# testboard_chip1_poling.net
KiCad netlist of a schematic drawn in Altium Designer
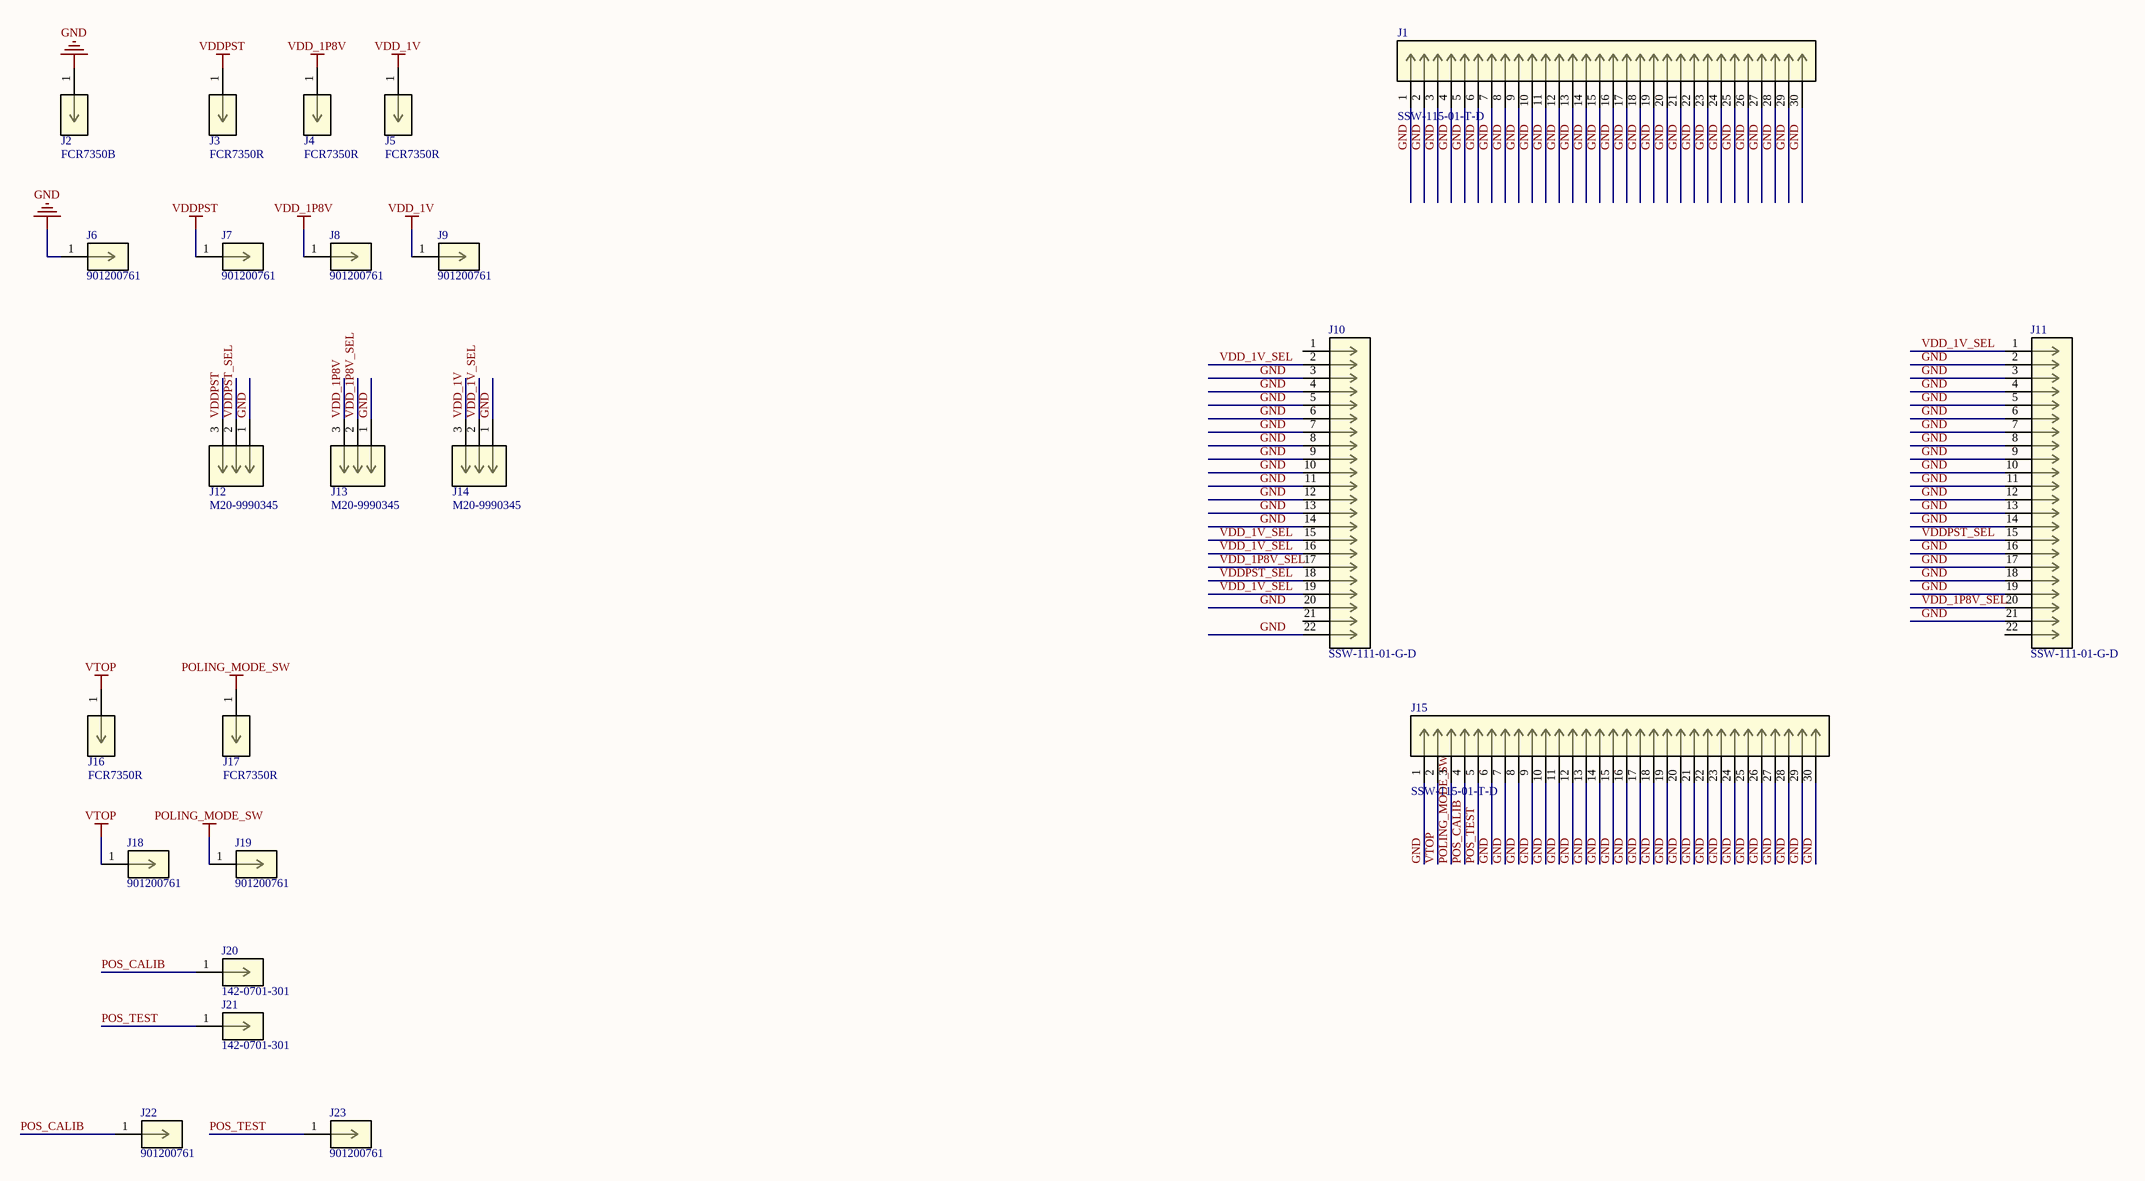
[diagram p0: testboard_chip1_poling.SchDoc]

(export (version "E")
  (design (tool "Eeschema 10.0.6"))
  (components
    (comp (ref "J1")
      (value "SSW-115-01-T-D")
      (footprint "CON30_2X15_TU_SSQ")
      (description "No Description Available")
      (fields (field (name "COPYRIGHT") "Copyright (C) 2022 Ultra Librarian. All rights reserved."))
      (libsource (lib "SSW-115-01-T-D") (part "SSW-115-01-T-D"))
    )
    (comp (ref "J2")
      (value "FCR7350B")
      (footprint "CONN1_FCR7350R_CLF")
      (description "No Description Available")
      (fields
        (field (name "MANUFACTURER_PART_NUMBER") "FCR7350R")
        (field (name "COPYRIGHT") "Copyright (C) 2022 Ultra Librarian. All rights reserved.")
      )
      (libsource (lib "FCR7350B") (part "FCR7350R"))
    )
    (comp (ref "J3")
      (value "FCR7350R")
      (footprint "CONN1_FCR7350R_CLF")
      (description "No Description Available")
      (fields (field (name "COPYRIGHT") "Copyright (C) 2022 Ultra Librarian. All rights reserved."))
      (libsource (lib "FCR7350R") (part "FCR7350R"))
    )
    (comp (ref "J4")
      (value "FCR7350R")
      (footprint "CONN1_FCR7350R_CLF")
      (description "No Description Available")
      (fields (field (name "COPYRIGHT") "Copyright (C) 2022 Ultra Librarian. All rights reserved."))
      (libsource (lib "FCR7350R") (part "FCR7350R"))
    )
    (comp (ref "J5")
      (value "FCR7350R")
      (footprint "CONN1_FCR7350R_CLF")
      (description "No Description Available")
      (fields (field (name "COPYRIGHT") "Copyright (C) 2022 Ultra Librarian. All rights reserved."))
      (libsource (lib "FCR7350R") (part "FCR7350R"))
    )
    (comp (ref "J6")
      (value "901200761")
      (footprint "CONN_90120-0761_MOL")
      (description "No Description Available")
      (fields (field (name "COPYRIGHT") "Copyright (C) 2022 Ultra Librarian. All rights reserved."))
      (libsource (lib "901200761") (part "901200761"))
    )
    (comp (ref "J7")
      (value "901200761")
      (footprint "CONN_90120-0761_MOL")
      (description "No Description Available")
      (fields (field (name "COPYRIGHT") "Copyright (C) 2022 Ultra Librarian. All rights reserved."))
      (libsource (lib "901200761") (part "901200761"))
    )
    (comp (ref "J8")
      (value "901200761")
      (footprint "CONN_90120-0761_MOL")
      (description "No Description Available")
      (fields (field (name "COPYRIGHT") "Copyright (C) 2022 Ultra Librarian. All rights reserved."))
      (libsource (lib "901200761") (part "901200761"))
    )
    (comp (ref "J9")
      (value "901200761")
      (footprint "CONN_90120-0761_MOL")
      (description "No Description Available")
      (fields (field (name "COPYRIGHT") "Copyright (C) 2022 Ultra Librarian. All rights reserved."))
      (libsource (lib "901200761") (part "901200761"))
    )
    (comp (ref "J10")
      (value "SSW-111-01-G-D")
      (footprint "CON23_2X11_TU_SSQ")
      (description "No Description Available")
      (fields (field (name "COPYRIGHT") "Copyright (C) 2022 Ultra Librarian. All rights reserved."))
      (libsource (lib "SSW-111-01-G-D") (part "SSW-111-01-G-D"))
    )
    (comp (ref "J11")
      (value "SSW-111-01-G-D")
      (footprint "CON23_2X11_TU_SSQ")
      (description "No Description Available")
      (fields (field (name "COPYRIGHT") "Copyright (C) 2022 Ultra Librarian. All rights reserved."))
      (libsource (lib "SSW-111-01-G-D") (part "SSW-111-01-G-D"))
    )
    (comp (ref "J12")
      (value "M20-9990345")
      (footprint "CONN_M20-99903XX_HRW")
      (description "No Description Available")
      (fields (field (name "COPYRIGHT") "Copyright (C) 2022 Ultra Librarian. All rights reserved."))
      (libsource (lib "M20-9990345") (part "M20-9990345"))
    )
    (comp (ref "J13")
      (value "M20-9990345")
      (footprint "CONN_M20-99903XX_HRW")
      (description "No Description Available")
      (fields (field (name "COPYRIGHT") "Copyright (C) 2022 Ultra Librarian. All rights reserved."))
      (libsource (lib "M20-9990345") (part "M20-9990345"))
    )
    (comp (ref "J14")
      (value "M20-9990345")
      (footprint "CONN_M20-99903XX_HRW")
      (description "No Description Available")
      (fields (field (name "COPYRIGHT") "Copyright (C) 2022 Ultra Librarian. All rights reserved."))
      (libsource (lib "M20-9990345") (part "M20-9990345"))
    )
    (comp (ref "J15")
      (value "SSW-115-01-T-D")
      (footprint "CON30_2X15_TU_SSQ")
      (description "No Description Available")
      (fields (field (name "COPYRIGHT") "Copyright (C) 2022 Ultra Librarian. All rights reserved."))
      (libsource (lib "SSW-115-01-T-D") (part "SSW-115-01-T-D"))
    )
    (comp (ref "J16")
      (value "FCR7350R")
      (footprint "CONN1_FCR7350R_CLF")
      (description "No Description Available")
      (fields (field (name "COPYRIGHT") "Copyright (C) 2022 Ultra Librarian. All rights reserved."))
      (libsource (lib "FCR7350R") (part "FCR7350R"))
    )
    (comp (ref "J17")
      (value "FCR7350R")
      (footprint "CONN1_FCR7350R_CLF")
      (description "No Description Available")
      (fields (field (name "COPYRIGHT") "Copyright (C) 2022 Ultra Librarian. All rights reserved."))
      (libsource (lib "FCR7350R") (part "FCR7350R"))
    )
    (comp (ref "J18")
      (value "901200761")
      (footprint "CONN_90120-0761_MOL")
      (description "No Description Available")
      (fields (field (name "COPYRIGHT") "Copyright (C) 2022 Ultra Librarian. All rights reserved."))
      (libsource (lib "901200761") (part "901200761"))
    )
    (comp (ref "J19")
      (value "901200761")
      (footprint "CONN_90120-0761_MOL")
      (description "No Description Available")
      (fields (field (name "COPYRIGHT") "Copyright (C) 2022 Ultra Librarian. All rights reserved."))
      (libsource (lib "901200761") (part "901200761"))
    )
    (comp (ref "J20")
      (value "142-0701-301")
      (footprint "CONN_142-0701-301_CIN")
      (description "No Description Available")
      (fields (field (name "COPYRIGHT") "Copyright (C) 2022 Ultra Librarian. All rights reserved."))
      (libsource (lib "142-0701-301") (part "142-0701-301"))
    )
    (comp (ref "J21")
      (value "142-0701-301")
      (footprint "CONN_142-0701-301_CIN")
      (description "No Description Available")
      (fields (field (name "COPYRIGHT") "Copyright (C) 2022 Ultra Librarian. All rights reserved."))
      (libsource (lib "142-0701-301") (part "142-0701-301"))
    )
    (comp (ref "J22")
      (value "901200761")
      (footprint "CONN_90120-0761_MOL")
      (description "No Description Available")
      (fields (field (name "COPYRIGHT") "Copyright (C) 2022 Ultra Librarian. All rights reserved."))
      (libsource (lib "901200761") (part "901200761"))
    )
    (comp (ref "J23")
      (value "901200761")
      (footprint "CONN_90120-0761_MOL")
      (description "No Description Available")
      (fields (field (name "COPYRIGHT") "Copyright (C) 2022 Ultra Librarian. All rights reserved."))
      (libsource (lib "901200761") (part "901200761"))
    )
  )
  (nets
    (net (code "1") (name "/POS_CALIB") (class "Default")
      (node (ref "J15") (pin "4") (pinfunction "4_4") (pintype "passive"))
      (node (ref "J20") (pin "1") (pinfunction "1_1") (pintype "passive"))
      (node (ref "J22") (pin "1") (pinfunction "1_1") (pintype "passive"))
    )
    (net (code "2") (name "/POS_TEST") (class "Default")
      (node (ref "J15") (pin "5") (pinfunction "5_5") (pintype "passive"))
      (node (ref "J21") (pin "1") (pinfunction "1_1") (pintype "passive"))
      (node (ref "J23") (pin "1") (pinfunction "1_1") (pintype "passive"))
    )
    (net (code "3") (name "/VDDPST_SEL") (class "Default")
      (node (ref "J10") (pin "18") (pinfunction "18_18") (pintype "passive"))
      (node (ref "J11") (pin "15") (pinfunction "15_15") (pintype "passive"))
      (node (ref "J12") (pin "2") (pinfunction "2_2") (pintype "passive"))
    )
    (net (code "4") (name "/VDD_1P8V_SEL") (class "Default")
      (node (ref "J10") (pin "17") (pinfunction "17_17") (pintype "passive"))
      (node (ref "J11") (pin "20") (pinfunction "20_20") (pintype "passive"))
      (node (ref "J13") (pin "2") (pinfunction "2_2") (pintype "passive"))
    )
    (net (code "5") (name "/VDD_1V_SEL") (class "Default")
      (node (ref "J10") (pin "15") (pinfunction "15_15") (pintype "passive"))
      (node (ref "J10") (pin "16") (pinfunction "16_16") (pintype "passive"))
      (node (ref "J10") (pin "19") (pinfunction "19_19") (pintype "passive"))
      (node (ref "J10") (pin "2") (pinfunction "2_2") (pintype "passive"))
      (node (ref "J11") (pin "1") (pinfunction "1_1") (pintype "passive"))
      (node (ref "J14") (pin "2") (pinfunction "2_2") (pintype "passive"))
    )
    (net (code "6") (name "GND") (class "Default")
      (node (ref "J1") (pin "1") (pinfunction "1_1") (pintype "passive"))
      (node (ref "J1") (pin "10") (pinfunction "10_10") (pintype "passive"))
      (node (ref "J1") (pin "11") (pinfunction "11_11") (pintype "passive"))
      (node (ref "J1") (pin "12") (pinfunction "12_12") (pintype "passive"))
      (node (ref "J1") (pin "13") (pinfunction "13_13") (pintype "passive"))
      (node (ref "J1") (pin "14") (pinfunction "14_14") (pintype "passive"))
      (node (ref "J1") (pin "15") (pinfunction "15_15") (pintype "passive"))
      (node (ref "J1") (pin "16") (pinfunction "16_16") (pintype "passive"))
      (node (ref "J1") (pin "17") (pinfunction "17_17") (pintype "passive"))
      (node (ref "J1") (pin "18") (pinfunction "18_18") (pintype "passive"))
      (node (ref "J1") (pin "19") (pinfunction "19_19") (pintype "passive"))
      (node (ref "J1") (pin "2") (pinfunction "2_2") (pintype "passive"))
      (node (ref "J1") (pin "20") (pinfunction "20_20") (pintype "passive"))
      (node (ref "J1") (pin "21") (pinfunction "21_21") (pintype "passive"))
      (node (ref "J1") (pin "22") (pinfunction "22_22") (pintype "passive"))
      (node (ref "J1") (pin "23") (pinfunction "23_23") (pintype "passive"))
      (node (ref "J1") (pin "24") (pinfunction "24_24") (pintype "passive"))
      (node (ref "J1") (pin "25") (pinfunction "25_25") (pintype "passive"))
      (node (ref "J1") (pin "26") (pinfunction "26_26") (pintype "passive"))
      (node (ref "J1") (pin "27") (pinfunction "27_27") (pintype "passive"))
      (node (ref "J1") (pin "28") (pinfunction "28_28") (pintype "passive"))
      (node (ref "J1") (pin "29") (pinfunction "29_29") (pintype "passive"))
      (node (ref "J1") (pin "3") (pinfunction "3_3") (pintype "passive"))
      (node (ref "J1") (pin "30") (pinfunction "30_30") (pintype "passive"))
      (node (ref "J1") (pin "4") (pinfunction "4_4") (pintype "passive"))
      (node (ref "J1") (pin "5") (pinfunction "5_5") (pintype "passive"))
      (node (ref "J1") (pin "6") (pinfunction "6_6") (pintype "passive"))
      (node (ref "J1") (pin "7") (pinfunction "7_7") (pintype "passive"))
      (node (ref "J1") (pin "8") (pinfunction "8_8") (pintype "passive"))
      (node (ref "J1") (pin "9") (pinfunction "9_9") (pintype "passive"))
      (node (ref "J10") (pin "10") (pinfunction "10_10") (pintype "passive"))
      (node (ref "J10") (pin "11") (pinfunction "11_11") (pintype "passive"))
      (node (ref "J10") (pin "12") (pinfunction "12_12") (pintype "passive"))
      (node (ref "J10") (pin "13") (pinfunction "13_13") (pintype "passive"))
      (node (ref "J10") (pin "14") (pinfunction "14_14") (pintype "passive"))
      (node (ref "J10") (pin "20") (pinfunction "20_20") (pintype "passive"))
      (node (ref "J10") (pin "22") (pinfunction "22_22") (pintype "passive"))
      (node (ref "J10") (pin "3") (pinfunction "3_3") (pintype "passive"))
      (node (ref "J10") (pin "4") (pinfunction "4_4") (pintype "passive"))
      (node (ref "J10") (pin "5") (pinfunction "5_5") (pintype "passive"))
      (node (ref "J10") (pin "6") (pinfunction "6_6") (pintype "passive"))
      (node (ref "J10") (pin "7") (pinfunction "7_7") (pintype "passive"))
      (node (ref "J10") (pin "8") (pinfunction "8_8") (pintype "passive"))
      (node (ref "J10") (pin "9") (pinfunction "9_9") (pintype "passive"))
      (node (ref "J11") (pin "10") (pinfunction "10_10") (pintype "passive"))
      (node (ref "J11") (pin "11") (pinfunction "11_11") (pintype "passive"))
      (node (ref "J11") (pin "12") (pinfunction "12_12") (pintype "passive"))
      (node (ref "J11") (pin "13") (pinfunction "13_13") (pintype "passive"))
      (node (ref "J11") (pin "14") (pinfunction "14_14") (pintype "passive"))
      (node (ref "J11") (pin "16") (pinfunction "16_16") (pintype "passive"))
      (node (ref "J11") (pin "17") (pinfunction "17_17") (pintype "passive"))
      (node (ref "J11") (pin "18") (pinfunction "18_18") (pintype "passive"))
      (node (ref "J11") (pin "19") (pinfunction "19_19") (pintype "passive"))
      (node (ref "J11") (pin "2") (pinfunction "2_2") (pintype "passive"))
      (node (ref "J11") (pin "21") (pinfunction "21_21") (pintype "passive"))
      (node (ref "J11") (pin "3") (pinfunction "3_3") (pintype "passive"))
      (node (ref "J11") (pin "4") (pinfunction "4_4") (pintype "passive"))
      (node (ref "J11") (pin "5") (pinfunction "5_5") (pintype "passive"))
      (node (ref "J11") (pin "6") (pinfunction "6_6") (pintype "passive"))
      (node (ref "J11") (pin "7") (pinfunction "7_7") (pintype "passive"))
      (node (ref "J11") (pin "8") (pinfunction "8_8") (pintype "passive"))
      (node (ref "J11") (pin "9") (pinfunction "9_9") (pintype "passive"))
      (node (ref "J12") (pin "1") (pinfunction "1_1") (pintype "passive"))
      (node (ref "J13") (pin "1") (pinfunction "1_1") (pintype "passive"))
      (node (ref "J14") (pin "1") (pinfunction "1_1") (pintype "passive"))
      (node (ref "J15") (pin "1") (pinfunction "1_1") (pintype "passive"))
      (node (ref "J15") (pin "10") (pinfunction "10_10") (pintype "passive"))
      (node (ref "J15") (pin "11") (pinfunction "11_11") (pintype "passive"))
      (node (ref "J15") (pin "12") (pinfunction "12_12") (pintype "passive"))
      (node (ref "J15") (pin "13") (pinfunction "13_13") (pintype "passive"))
      (node (ref "J15") (pin "14") (pinfunction "14_14") (pintype "passive"))
      (node (ref "J15") (pin "15") (pinfunction "15_15") (pintype "passive"))
      (node (ref "J15") (pin "16") (pinfunction "16_16") (pintype "passive"))
      (node (ref "J15") (pin "17") (pinfunction "17_17") (pintype "passive"))
      (node (ref "J15") (pin "18") (pinfunction "18_18") (pintype "passive"))
      (node (ref "J15") (pin "19") (pinfunction "19_19") (pintype "passive"))
      (node (ref "J15") (pin "20") (pinfunction "20_20") (pintype "passive"))
      (node (ref "J15") (pin "21") (pinfunction "21_21") (pintype "passive"))
      (node (ref "J15") (pin "22") (pinfunction "22_22") (pintype "passive"))
      (node (ref "J15") (pin "23") (pinfunction "23_23") (pintype "passive"))
      (node (ref "J15") (pin "24") (pinfunction "24_24") (pintype "passive"))
      (node (ref "J15") (pin "25") (pinfunction "25_25") (pintype "passive"))
      (node (ref "J15") (pin "26") (pinfunction "26_26") (pintype "passive"))
      (node (ref "J15") (pin "27") (pinfunction "27_27") (pintype "passive"))
      (node (ref "J15") (pin "28") (pinfunction "28_28") (pintype "passive"))
      (node (ref "J15") (pin "29") (pinfunction "29_29") (pintype "passive"))
      (node (ref "J15") (pin "30") (pinfunction "30_30") (pintype "passive"))
      (node (ref "J15") (pin "6") (pinfunction "6_6") (pintype "passive"))
      (node (ref "J15") (pin "7") (pinfunction "7_7") (pintype "passive"))
      (node (ref "J15") (pin "8") (pinfunction "8_8") (pintype "passive"))
      (node (ref "J15") (pin "9") (pinfunction "9_9") (pintype "passive"))
      (node (ref "J2") (pin "1") (pinfunction "1_1") (pintype "passive"))
      (node (ref "J6") (pin "1") (pinfunction "1_1") (pintype "passive"))
    )
    (net (code "7") (name "POLING_MODE_SW") (class "Default")
      (node (ref "J15") (pin "3") (pinfunction "3_3") (pintype "passive"))
      (node (ref "J17") (pin "1") (pinfunction "1_1") (pintype "passive"))
      (node (ref "J19") (pin "1") (pinfunction "1_1") (pintype "passive"))
    )
    (net (code "8") (name "VDDPST") (class "Default")
      (node (ref "J12") (pin "3") (pinfunction "3_3") (pintype "passive"))
      (node (ref "J3") (pin "1") (pinfunction "1_1") (pintype "passive"))
      (node (ref "J7") (pin "1") (pinfunction "1_1") (pintype "passive"))
    )
    (net (code "9") (name "VDD_1P8V") (class "Default")
      (node (ref "J13") (pin "3") (pinfunction "3_3") (pintype "passive"))
      (node (ref "J4") (pin "1") (pinfunction "1_1") (pintype "passive"))
      (node (ref "J8") (pin "1") (pinfunction "1_1") (pintype "passive"))
    )
    (net (code "10") (name "VDD_1V") (class "Default")
      (node (ref "J14") (pin "3") (pinfunction "3_3") (pintype "passive"))
      (node (ref "J5") (pin "1") (pinfunction "1_1") (pintype "passive"))
      (node (ref "J9") (pin "1") (pinfunction "1_1") (pintype "passive"))
    )
    (net (code "11") (name "VTOP") (class "Default")
      (node (ref "J15") (pin "2") (pinfunction "2_2") (pintype "passive"))
      (node (ref "J16") (pin "1") (pinfunction "1_1") (pintype "passive"))
      (node (ref "J18") (pin "1") (pinfunction "1_1") (pintype "passive"))
    )
    (net (code "12") (name "unconnected-(J10-Pad1)") (class "Default")
      (node (ref "J10") (pin "1") (pinfunction "1_1") (pintype "passive"))
    )
    (net (code "13") (name "unconnected-(J10-Pad21)") (class "Default")
      (node (ref "J10") (pin "21") (pinfunction "21_21") (pintype "passive"))
    )
    (net (code "14") (name "unconnected-(J11-Pad22)") (class "Default")
      (node (ref "J11") (pin "22") (pinfunction "22_22") (pintype "passive"))
    )
  )
)
